# Passive_Mult.net
KiCad netlist of a schematic drawn in EAGLE
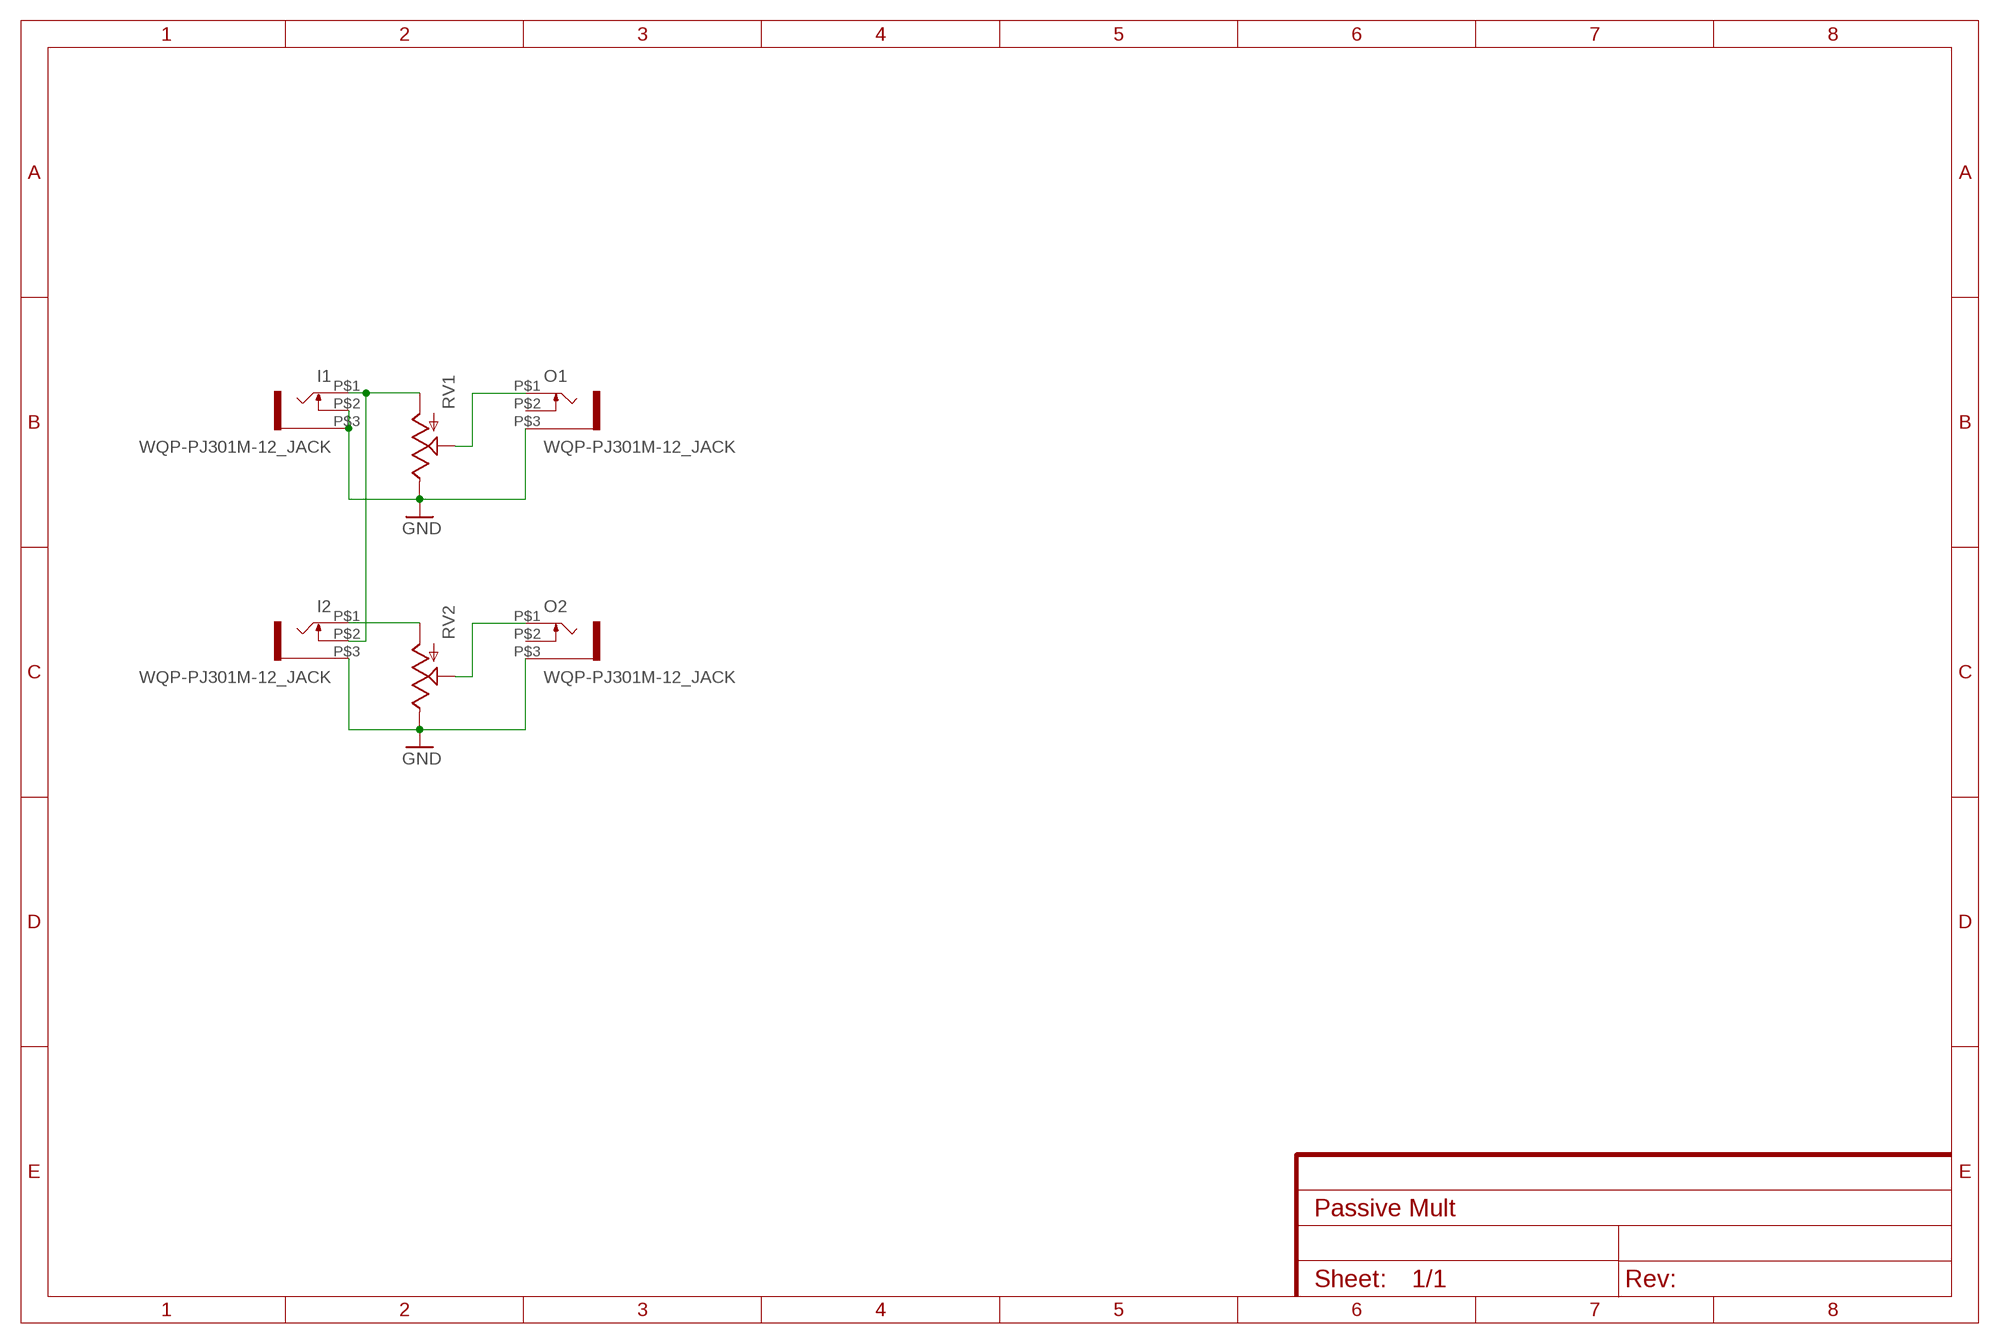
[diagram p0: schematic, sheet 1]

(export (version "E")
  (design (tool "Eeschema 10.0.6"))
  (components
    (comp (ref "I1")
      (value "WQP-PJ301M-12_JACK")
      (footprint "eagle-import:WQP-PJ301M-12_JACK")
      (libsource (lib "eagle-import") (part "WQP-PJ301M-12_JACK"))
    )
    (comp (ref "I2")
      (value "WQP-PJ301M-12_JACK")
      (footprint "eagle-import:WQP-PJ301M-12_JACK")
      (libsource (lib "eagle-import") (part "WQP-PJ301M-12_JACK"))
    )
    (comp (ref "O1")
      (value "WQP-PJ301M-12_JACK")
      (footprint "eagle-import:WQP-PJ301M-12_JACK")
      (libsource (lib "eagle-import") (part "WQP-PJ301M-12_JACK"))
    )
    (comp (ref "O2")
      (value "WQP-PJ301M-12_JACK")
      (footprint "eagle-import:WQP-PJ301M-12_JACK")
      (libsource (lib "eagle-import") (part "WQP-PJ301M-12_JACK"))
    )
    (comp (ref "RV1")
      (value "POT_NO_CLIP")
      (footprint "eagle-import:ALPS_POT_NO_CLIPS")
      (libsource (lib "eagle-import") (part "POT_NO_CLIP"))
    )
    (comp (ref "RV2")
      (value "POT_NO_CLIP")
      (footprint "eagle-import:ALPS_POT_NO_CLIPS")
      (libsource (lib "eagle-import") (part "POT_NO_CLIP"))
    )
  )
  (nets
    (net (code "1") (name "GND") (class "Default")
      (node (ref "I1") (pin "P$2") (pinfunction "3_P$2") (pintype "passive"))
      (node (ref "I1") (pin "P$3") (pinfunction "1_P$3") (pintype "passive"))
      (node (ref "I2") (pin "P$3") (pinfunction "1_P$3") (pintype "passive"))
      (node (ref "O1") (pin "P$3") (pinfunction "1_P$3") (pintype "passive"))
      (node (ref "O2") (pin "P$3") (pinfunction "1_P$3") (pintype "passive"))
      (node (ref "RV1") (pin "P$1") (pinfunction "E_P$1") (pintype "passive"))
      (node (ref "RV2") (pin "P$1") (pinfunction "E_P$1") (pintype "passive"))
    )
    (net (code "2") (name "Net-(I1-2)") (class "Default")
      (node (ref "I1") (pin "P$1") (pinfunction "2_P$1") (pintype "passive"))
      (node (ref "I2") (pin "P$2") (pinfunction "3_P$2") (pintype "passive"))
      (node (ref "RV1") (pin "P$3") (pinfunction "A_P$3") (pintype "passive"))
    )
    (net (code "3") (name "Net-(I2-2)") (class "Default")
      (node (ref "I2") (pin "P$1") (pinfunction "2_P$1") (pintype "passive"))
      (node (ref "RV2") (pin "P$3") (pinfunction "A_P$3") (pintype "passive"))
    )
    (net (code "4") (name "Net-(O1-2)") (class "Default")
      (node (ref "O1") (pin "P$1") (pinfunction "2_P$1") (pintype "passive"))
      (node (ref "RV1") (pin "P$2") (pinfunction "S_P$2") (pintype "passive"))
    )
    (net (code "5") (name "Net-(O2-2)") (class "Default")
      (node (ref "O2") (pin "P$1") (pinfunction "2_P$1") (pintype "passive"))
      (node (ref "RV2") (pin "P$2") (pinfunction "S_P$2") (pintype "passive"))
    )
    (net (code "6") (name "unconnected-(O1-3-PadP$2)") (class "Default")
      (node (ref "O1") (pin "P$2") (pinfunction "3_P$2") (pintype "passive"))
    )
    (net (code "7") (name "unconnected-(O2-3-PadP$2)") (class "Default")
      (node (ref "O2") (pin "P$2") (pinfunction "3_P$2") (pintype "passive"))
    )
  )
)
